# main.net
KiCad netlist of a schematic drawn in EAGLE
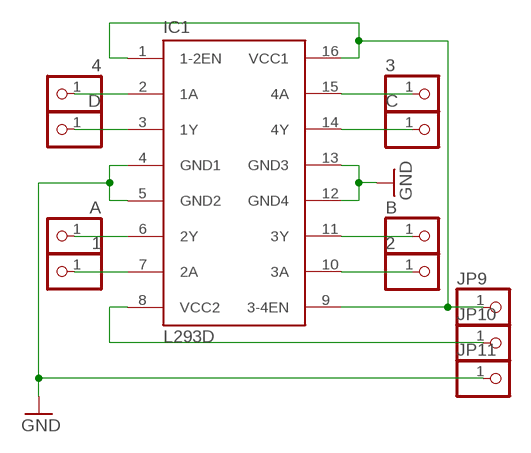
[diagram p0: schematic, sheet 1]

(export (version "E")
  (design (tool "Eeschema 10.0.6"))
  (components
    (comp (ref "1")
      (value "PINHD-1X1")
      (footprint "eagle-import:1X01")
      (libsource (lib "eagle-import") (part "PINHD-1X1"))
    )
    (comp (ref "2")
      (value "PINHD-1X1")
      (footprint "eagle-import:1X01")
      (libsource (lib "eagle-import") (part "PINHD-1X1"))
    )
    (comp (ref "3")
      (value "PINHD-1X1")
      (footprint "eagle-import:1X01")
      (libsource (lib "eagle-import") (part "PINHD-1X1"))
    )
    (comp (ref "4")
      (value "PINHD-1X1")
      (footprint "eagle-import:1X01")
      (libsource (lib "eagle-import") (part "PINHD-1X1"))
    )
    (comp (ref "A")
      (value "PINHD-1X1")
      (footprint "eagle-import:1X01")
      (libsource (lib "eagle-import") (part "PINHD-1X1"))
    )
    (comp (ref "B")
      (value "PINHD-1X1")
      (footprint "eagle-import:1X01")
      (libsource (lib "eagle-import") (part "PINHD-1X1"))
    )
    (comp (ref "C")
      (value "PINHD-1X1")
      (footprint "eagle-import:1X01")
      (libsource (lib "eagle-import") (part "PINHD-1X1"))
    )
    (comp (ref "D")
      (value "PINHD-1X1")
      (footprint "eagle-import:1X01")
      (libsource (lib "eagle-import") (part "PINHD-1X1"))
    )
    (comp (ref "IC1")
      (value "L293D")
      (footprint "eagle-import:DIL16")
      (libsource (lib "eagle-import") (part "L293D"))
    )
    (comp (ref "JP9")
      (value "PINHD-1X1")
      (footprint "eagle-import:1X01")
      (libsource (lib "eagle-import") (part "PINHD-1X1"))
    )
    (comp (ref "JP10")
      (value "PINHD-1X1")
      (footprint "eagle-import:1X01")
      (libsource (lib "eagle-import") (part "PINHD-1X1"))
    )
    (comp (ref "JP11")
      (value "PINHD-1X1")
      (footprint "eagle-import:1X01")
      (libsource (lib "eagle-import") (part "PINHD-1X1"))
    )
  )
  (nets
    (net (code "1") (name "GND") (class "Default")
      (node (ref "IC1") (pin "12") (pinfunction "GND4_12") (pintype "power_in"))
      (node (ref "IC1") (pin "13") (pinfunction "GND3_13") (pintype "power_in"))
      (node (ref "IC1") (pin "4") (pinfunction "GND1_4") (pintype "power_in"))
      (node (ref "IC1") (pin "5") (pinfunction "GND2_5") (pintype "power_in"))
      (node (ref "JP11") (pin "1") (pinfunction "1_1") (pintype "passive"))
    )
    (net (code "2") (name "Net-(IC1-1-2EN)") (class "Default")
      (node (ref "IC1") (pin "1") (pinfunction "1-2EN_1") (pintype "input"))
      (node (ref "IC1") (pin "16") (pinfunction "VCC1_16") (pintype "power_in"))
      (node (ref "IC1") (pin "9") (pinfunction "3-4EN_9") (pintype "input"))
      (node (ref "JP9") (pin "1") (pinfunction "1_1") (pintype "passive"))
    )
    (net (code "3") (name "Net-(IC1-1A)") (class "Default")
      (node (ref "4") (pin "1") (pinfunction "1_1") (pintype "passive"))
      (node (ref "IC1") (pin "2") (pinfunction "1A_2") (pintype "input"))
    )
    (net (code "4") (name "Net-(IC1-1Y)") (class "Default")
      (node (ref "D") (pin "1") (pinfunction "1_1") (pintype "passive"))
      (node (ref "IC1") (pin "3") (pinfunction "1Y_3") (pintype "output"))
    )
    (net (code "5") (name "Net-(IC1-2A)") (class "Default")
      (node (ref "1") (pin "1") (pinfunction "1_1") (pintype "passive"))
      (node (ref "IC1") (pin "7") (pinfunction "2A_7") (pintype "input"))
    )
    (net (code "6") (name "Net-(IC1-2Y)") (class "Default")
      (node (ref "A") (pin "1") (pinfunction "1_1") (pintype "passive"))
      (node (ref "IC1") (pin "6") (pinfunction "2Y_6") (pintype "output"))
    )
    (net (code "7") (name "Net-(IC1-3A)") (class "Default")
      (node (ref "2") (pin "1") (pinfunction "1_1") (pintype "passive"))
      (node (ref "IC1") (pin "10") (pinfunction "3A_10") (pintype "input"))
    )
    (net (code "8") (name "Net-(IC1-3Y)") (class "Default")
      (node (ref "B") (pin "1") (pinfunction "1_1") (pintype "passive"))
      (node (ref "IC1") (pin "11") (pinfunction "3Y_11") (pintype "output"))
    )
    (net (code "9") (name "Net-(IC1-4A)") (class "Default")
      (node (ref "3") (pin "1") (pinfunction "1_1") (pintype "passive"))
      (node (ref "IC1") (pin "15") (pinfunction "4A_15") (pintype "input"))
    )
    (net (code "10") (name "Net-(IC1-4Y)") (class "Default")
      (node (ref "C") (pin "1") (pinfunction "1_1") (pintype "passive"))
      (node (ref "IC1") (pin "14") (pinfunction "4Y_14") (pintype "output"))
    )
    (net (code "11") (name "Net-(IC1-VCC2)") (class "Default")
      (node (ref "IC1") (pin "8") (pinfunction "VCC2_8") (pintype "power_in"))
      (node (ref "JP10") (pin "1") (pinfunction "1_1") (pintype "passive"))
    )
  )
)
